# expresscard-breakout.net
KiCad netlist of a schematic drawn in EAGLE
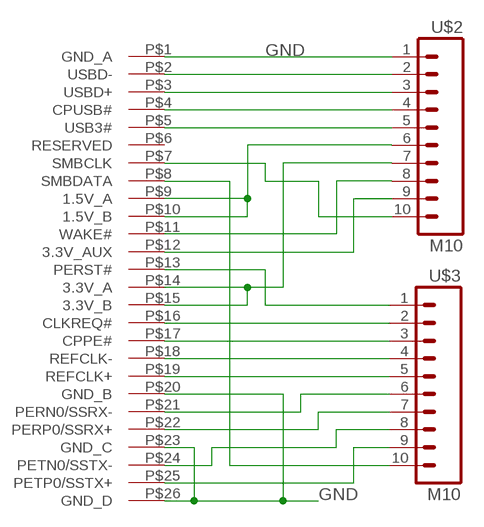
[diagram p0: schematic, sheet 1]

(export (version "E")
  (design (tool "Eeschema 10.0.6"))
  (components
    (comp (ref "U$1")
      (value "EXPRESSCARD34")
      (footprint "eagle-import:EXPRESSCARD34")
      (libsource (lib "eagle-import") (part "EXPRESSCARD34"))
    )
    (comp (ref "U$2")
      (value "M10")
      (footprint "eagle-import:1X10-SMD-NOHOLES")
      (libsource (lib "eagle-import") (part "M10"))
    )
    (comp (ref "U$3")
      (value "M10")
      (footprint "eagle-import:1X10-SMD-NOHOLES")
      (libsource (lib "eagle-import") (part "M10"))
    )
  )
  (nets
    (net (code "1") (name "/GND") (class "Default")
      (node (ref "U$1") (pin "P$1") (pinfunction "GND_A_P$1") (pintype "power_in"))
      (node (ref "U$1") (pin "P$20") (pinfunction "GND_B_P$20") (pintype "power_in"))
      (node (ref "U$1") (pin "P$23") (pinfunction "GND_C_P$23") (pintype "power_in"))
      (node (ref "U$1") (pin "P$26") (pinfunction "GND_D_P$26") (pintype "power_in"))
      (node (ref "U$2") (pin "1") (pinfunction "1_1") (pintype "passive"))
    )
    (net (code "2") (name "Net-(U$1-1.5V_A)") (class "Default")
      (node (ref "U$1") (pin "P$10") (pinfunction "1.5V_B_P$10") (pintype "power_in"))
      (node (ref "U$1") (pin "P$9") (pinfunction "1.5V_A_P$9") (pintype "power_in"))
      (node (ref "U$2") (pin "6") (pinfunction "6_6") (pintype "passive"))
    )
    (net (code "3") (name "Net-(U$1-3.3V_A)") (class "Default")
      (node (ref "U$1") (pin "P$14") (pinfunction "3.3V_A_P$14") (pintype "power_in"))
      (node (ref "U$1") (pin "P$15") (pinfunction "3.3V_B_P$15") (pintype "power_in"))
      (node (ref "U$2") (pin "7") (pinfunction "7_7") (pintype "passive"))
    )
    (net (code "4") (name "Net-(U$1-3.3V_AUX)") (class "Default")
      (node (ref "U$1") (pin "P$12") (pinfunction "3.3V_AUX_P$12") (pintype "power_in"))
      (node (ref "U$2") (pin "9") (pinfunction "9_9") (pintype "passive"))
    )
    (net (code "5") (name "Net-(U$1-CLKREQ#)") (class "Default")
      (node (ref "U$1") (pin "P$16") (pinfunction "CLKREQ#_P$16") (pintype "input"))
      (node (ref "U$3") (pin "2") (pinfunction "2_2") (pintype "passive"))
    )
    (net (code "6") (name "Net-(U$1-CPPE#)") (class "Default")
      (node (ref "U$1") (pin "P$17") (pinfunction "CPPE#_P$17") (pintype "input"))
      (node (ref "U$3") (pin "3") (pinfunction "3_3") (pintype "passive"))
    )
    (net (code "7") (name "Net-(U$1-CPUSB#)") (class "Default")
      (node (ref "U$1") (pin "P$4") (pinfunction "CPUSB#_P$4") (pintype "input"))
      (node (ref "U$2") (pin "4") (pinfunction "4_4") (pintype "passive"))
    )
    (net (code "8") (name "Net-(U$1-PERN0{slash}SSRX-)") (class "Default")
      (node (ref "U$1") (pin "P$21") (pinfunction "PERN0/SSRX-_P$21") (pintype "input"))
      (node (ref "U$3") (pin "6") (pinfunction "6_6") (pintype "passive"))
    )
    (net (code "9") (name "Net-(U$1-PERP0{slash}SSRX+)") (class "Default")
      (node (ref "U$1") (pin "P$22") (pinfunction "PERP0/SSRX+_P$22") (pintype "input"))
      (node (ref "U$3") (pin "7") (pinfunction "7_7") (pintype "passive"))
    )
    (net (code "10") (name "Net-(U$1-PERST#)") (class "Default")
      (node (ref "U$1") (pin "P$13") (pinfunction "PERST#_P$13") (pintype "output"))
      (node (ref "U$3") (pin "1") (pinfunction "1_1") (pintype "passive"))
    )
    (net (code "11") (name "Net-(U$1-PETN0{slash}SSTX-)") (class "Default")
      (node (ref "U$1") (pin "P$24") (pinfunction "PETN0/SSTX-_P$24") (pintype "output"))
      (node (ref "U$3") (pin "8") (pinfunction "8_8") (pintype "passive"))
    )
    (net (code "12") (name "Net-(U$1-PETP0{slash}SSTX+)") (class "Default")
      (node (ref "U$1") (pin "P$25") (pinfunction "PETP0/SSTX+_P$25") (pintype "output"))
      (node (ref "U$3") (pin "9") (pinfunction "9_9") (pintype "passive"))
    )
    (net (code "13") (name "Net-(U$1-REFCLK+)") (class "Default")
      (node (ref "U$1") (pin "P$19") (pinfunction "REFCLK+_P$19") (pintype "output"))
      (node (ref "U$3") (pin "5") (pinfunction "5_5") (pintype "passive"))
    )
    (net (code "14") (name "Net-(U$1-REFCLK-)") (class "Default")
      (node (ref "U$1") (pin "P$18") (pinfunction "REFCLK-_P$18") (pintype "output"))
      (node (ref "U$3") (pin "4") (pinfunction "4_4") (pintype "passive"))
    )
    (net (code "15") (name "Net-(U$1-SMBCLK)") (class "Default")
      (node (ref "U$1") (pin "P$7") (pinfunction "SMBCLK_P$7") (pintype "bidirectional"))
      (node (ref "U$2") (pin "10") (pinfunction "10_10") (pintype "passive"))
    )
    (net (code "16") (name "Net-(U$1-SMBDATA)") (class "Default")
      (node (ref "U$1") (pin "P$8") (pinfunction "SMBDATA_P$8") (pintype "bidirectional"))
      (node (ref "U$3") (pin "10") (pinfunction "10_10") (pintype "passive"))
    )
    (net (code "17") (name "Net-(U$1-USB3#)") (class "Default")
      (node (ref "U$1") (pin "P$5") (pinfunction "USB3#_P$5") (pintype "input"))
      (node (ref "U$2") (pin "5") (pinfunction "5_5") (pintype "passive"))
    )
    (net (code "18") (name "Net-(U$1-USBD+)") (class "Default")
      (node (ref "U$1") (pin "P$3") (pinfunction "USBD+_P$3") (pintype "bidirectional"))
      (node (ref "U$2") (pin "3") (pinfunction "3_3") (pintype "passive"))
    )
    (net (code "19") (name "Net-(U$1-USBD-)") (class "Default")
      (node (ref "U$1") (pin "P$2") (pinfunction "USBD-_P$2") (pintype "bidirectional"))
      (node (ref "U$2") (pin "2") (pinfunction "2_2") (pintype "passive"))
    )
    (net (code "20") (name "Net-(U$1-WAKE#)") (class "Default")
      (node (ref "U$1") (pin "P$11") (pinfunction "WAKE#_P$11") (pintype "input"))
      (node (ref "U$2") (pin "8") (pinfunction "8_8") (pintype "passive"))
    )
    (net (code "21") (name "unconnected-(U$1-RESERVED-PadP$6)") (class "Default")
      (node (ref "U$1") (pin "P$6") (pinfunction "RESERVED_P$6") (pintype "no_connect"))
    )
  )
)
